# main.net
KiCad netlist of a schematic drawn in Altium Designer
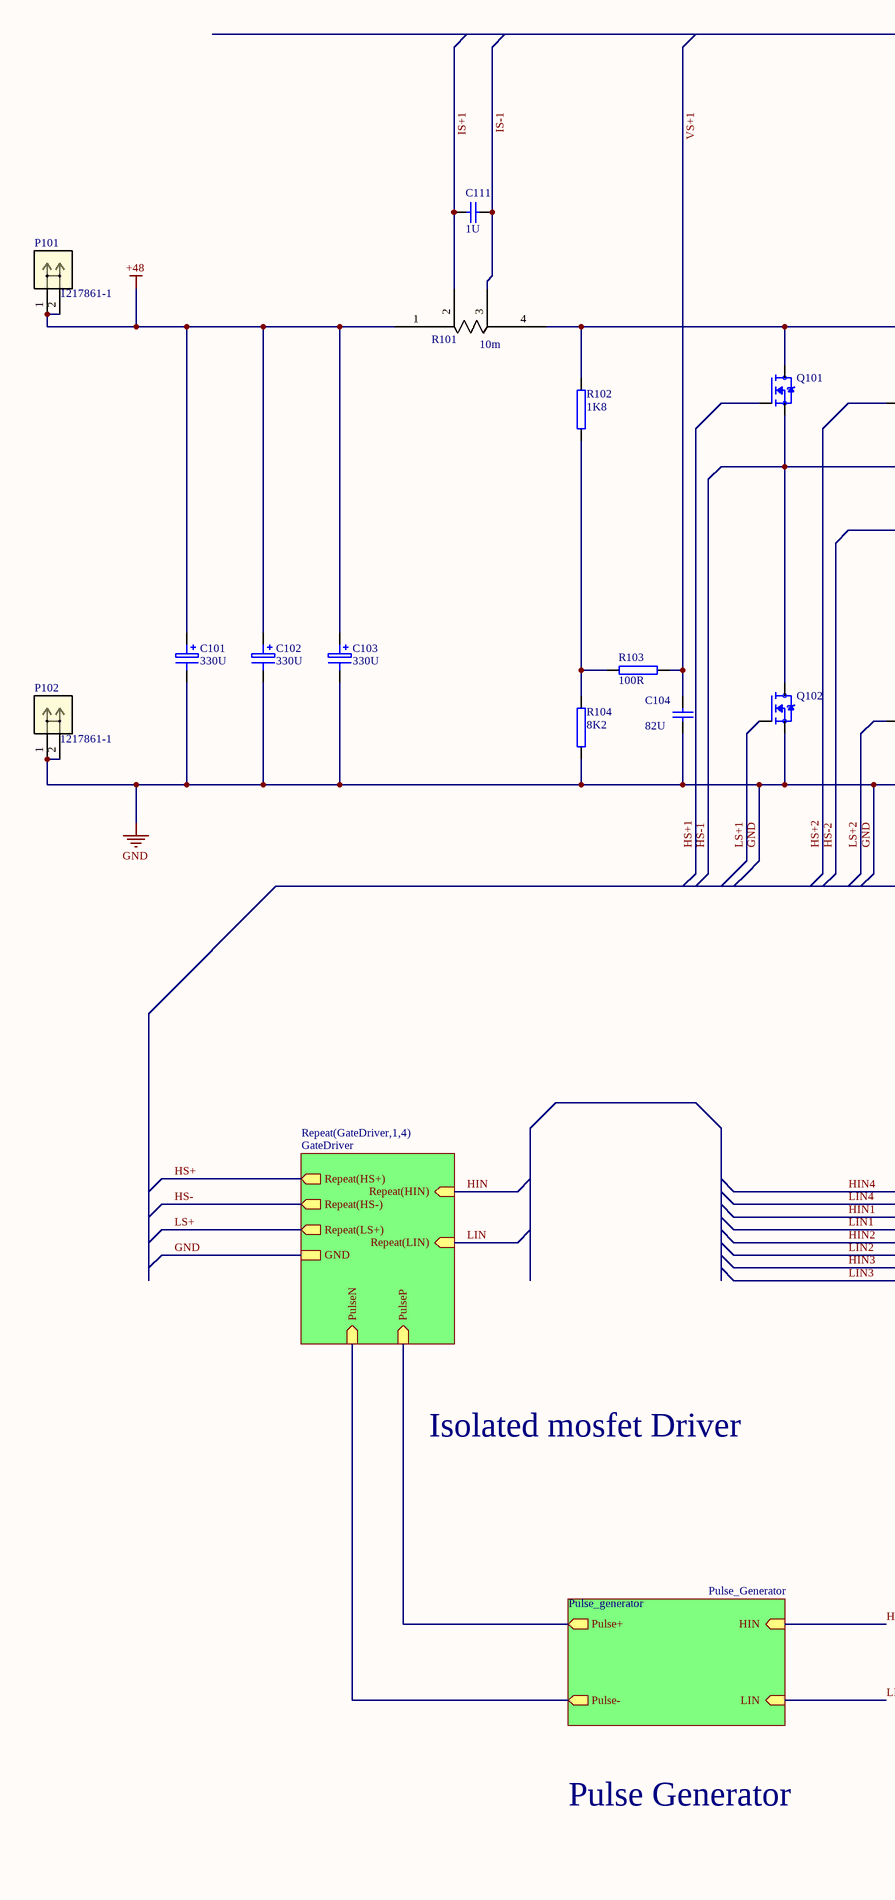
[diagram p0: main.SchDoc, left]
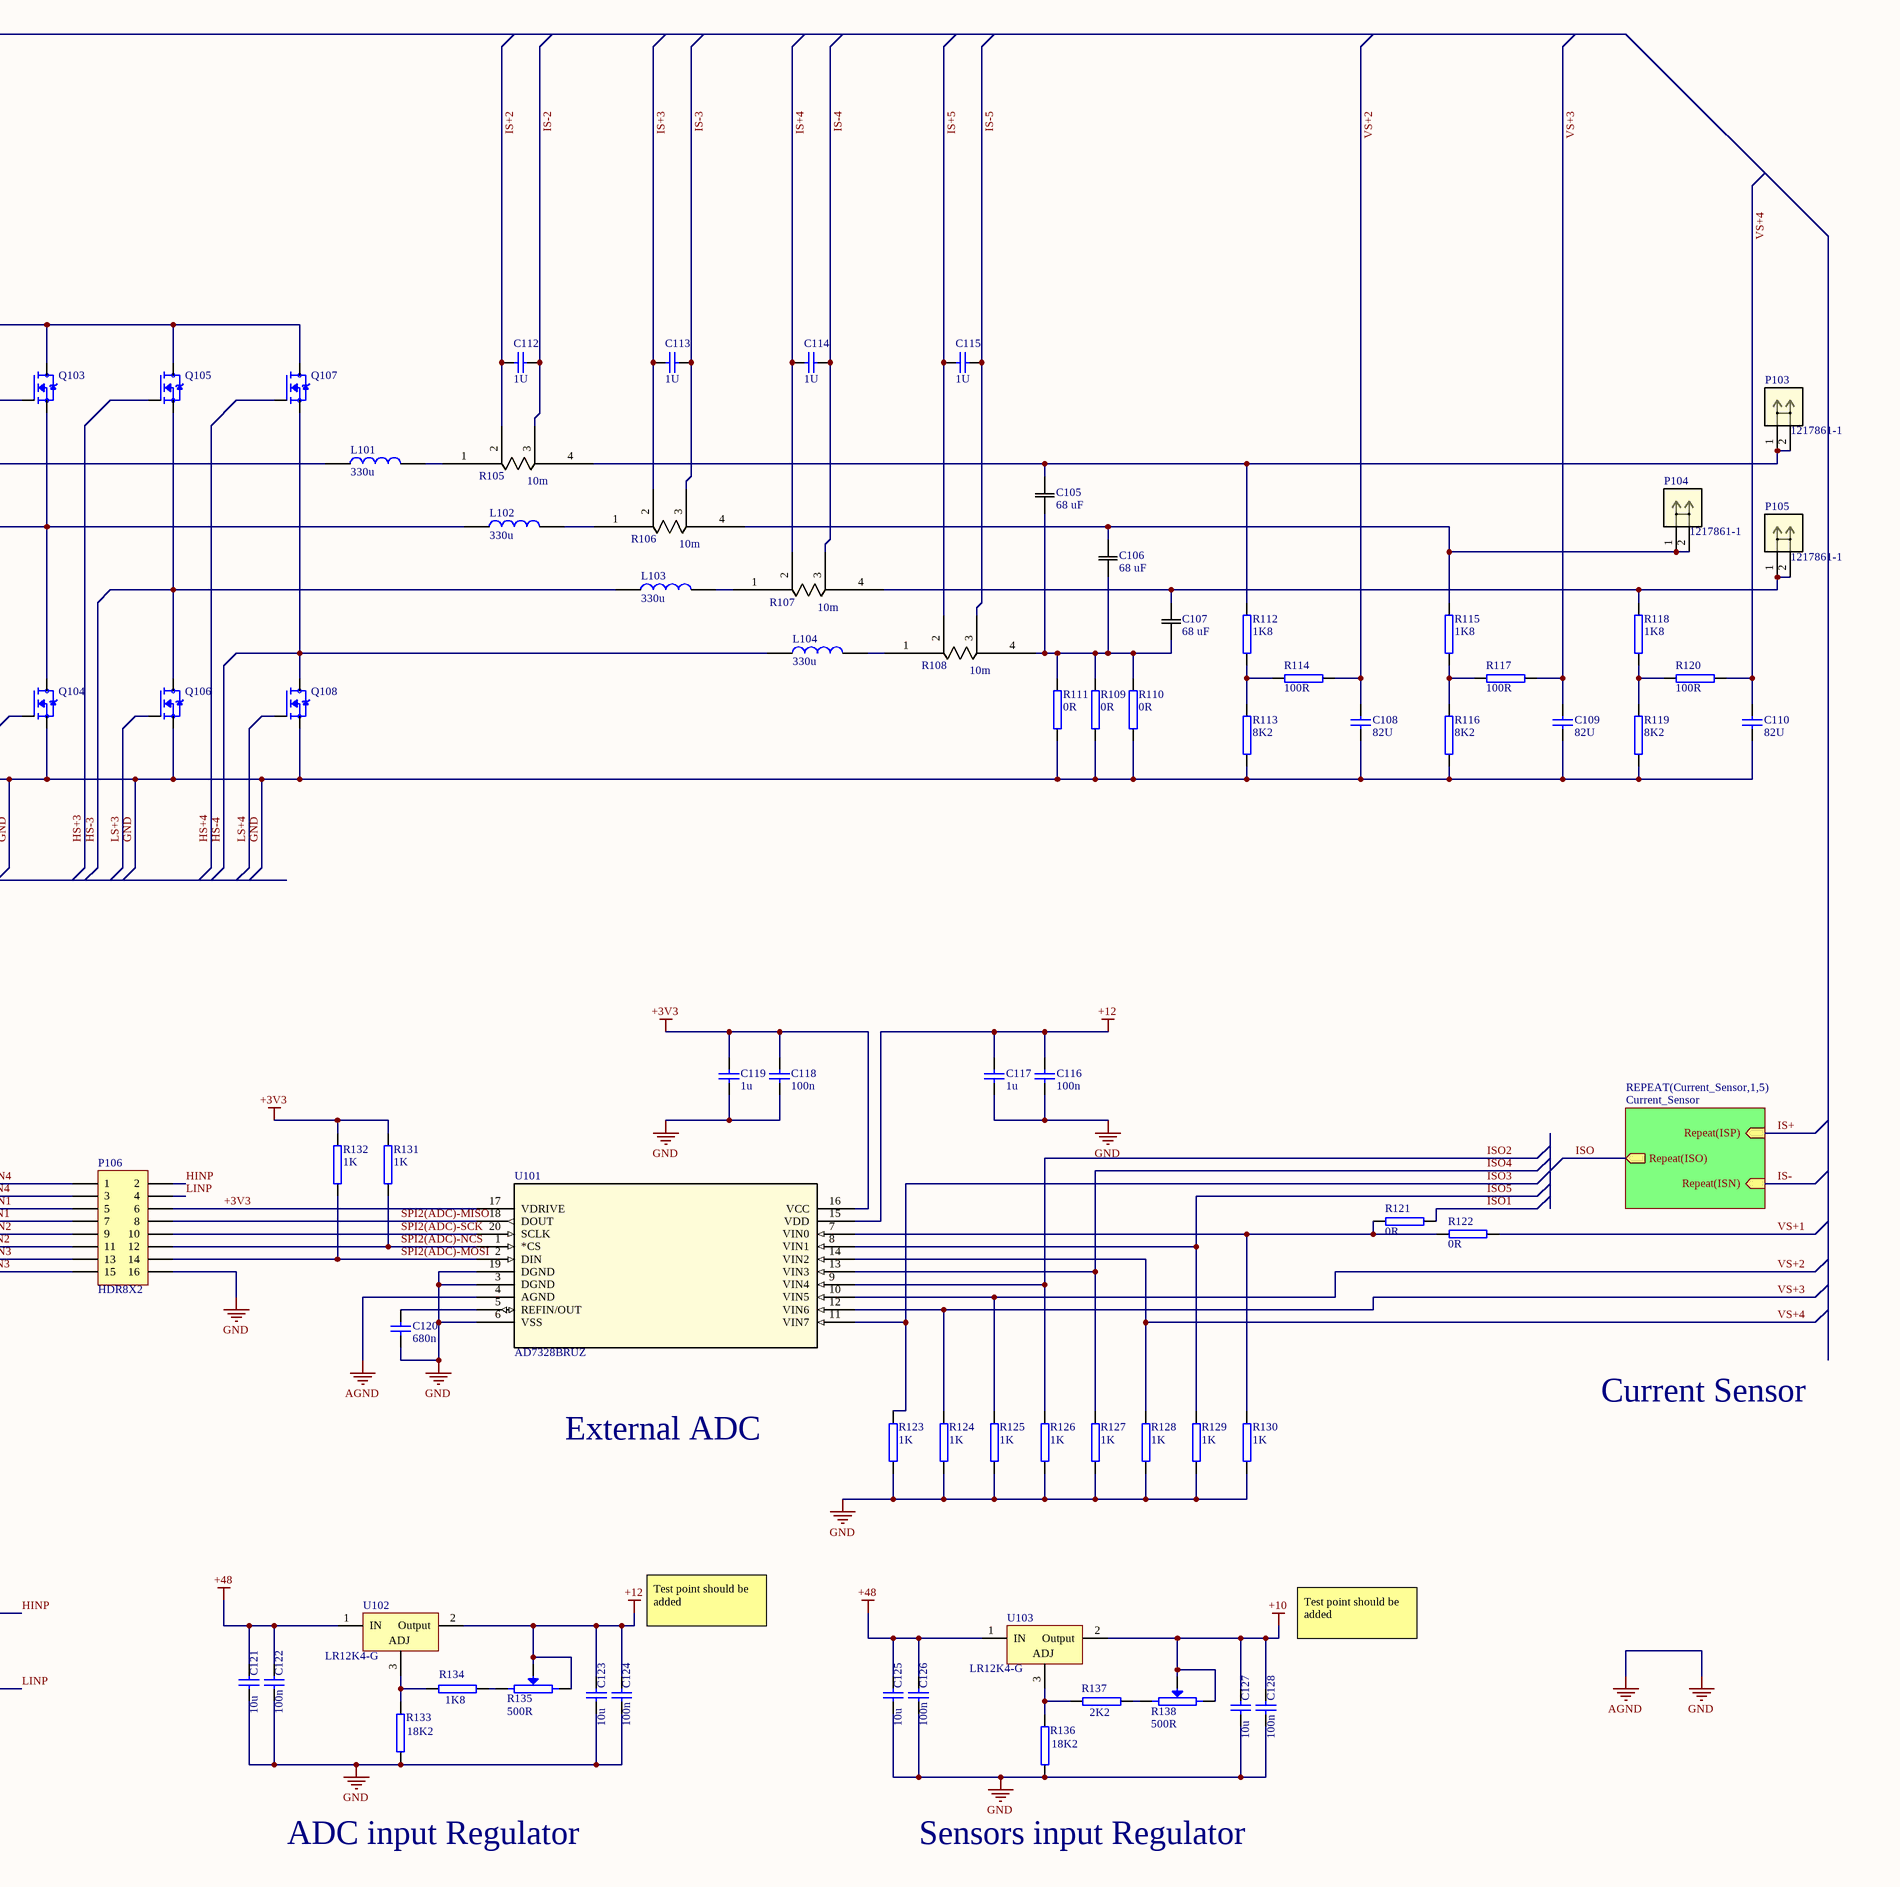
[diagram p1: main.SchDoc, right]

(export (version "E")
  (design (tool "Eeschema 10.0.6"))
  (components
    (comp (ref "C101")
      (value "330U")
      (footprint "CAPP300-600_AUT")
      (description "Polarized Aluminum Capacitor, Through Hole, Pitch 300mil, Body 600mil (Dia)")
      (libsource (lib "Resistors and Capacitors") (part "CAPP300-600"))
    )
    (comp (ref "C102")
      (value "330U")
      (footprint "CAPP300-600_AUT")
      (description "Polarized Aluminum Capacitor, Through Hole, Pitch 300mil, Body 600mil (Dia)")
      (libsource (lib "Resistors and Capacitors") (part "CAPP300-600"))
    )
    (comp (ref "C103")
      (value "330U")
      (footprint "CAPP300-600_AUT")
      (description "Polarized Aluminum Capacitor, Through Hole, Pitch 300mil, Body 600mil (Dia)")
      (libsource (lib "Resistors and Capacitors") (part "CAPP300-600"))
    )
    (comp (ref "C104")
      (value "82U")
      (footprint "CAP_1206")
      (description "Non Polarized Capacitor, SMD, 1206")
      (libsource (lib "Resistors and Capacitors") (part "CAPN 1206"))
    )
    (comp (ref "C105")
      (value "68 uF")
      (footprint "B32526R3686K000")
      (libsource (lib "ENEL709_Schematic_Library") (part "B32526R3686K000"))
    )
    (comp (ref "C106")
      (value "68 uF")
      (footprint "B32526R3686K000")
      (libsource (lib "ENEL709_Schematic_Library") (part "B32526R3686K000"))
    )
    (comp (ref "C107")
      (value "68 uF")
      (footprint "B32526R3686K000")
      (libsource (lib "ENEL709_Schematic_Library") (part "B32526R3686K000"))
    )
    (comp (ref "C108")
      (value "82U")
      (footprint "CAP_1206")
      (description "Non Polarized Capacitor, SMD, 1206")
      (libsource (lib "Resistors and Capacitors") (part "CAPN 1206"))
    )
    (comp (ref "C109")
      (value "82U")
      (footprint "CAP_1206")
      (description "Non Polarized Capacitor, SMD, 1206")
      (libsource (lib "Resistors and Capacitors") (part "CAPN 1206"))
    )
    (comp (ref "C110")
      (value "82U")
      (footprint "CAP_1206")
      (description "Non Polarized Capacitor, SMD, 1206")
      (libsource (lib "Resistors and Capacitors") (part "CAPN 1206"))
    )
    (comp (ref "C111")
      (value "1U")
      (footprint "CAP_1206")
      (description "Non Polarized Capacitor, SMD, 1206")
      (libsource (lib "Resistors and Capacitors") (part "CAPN 1206"))
    )
    (comp (ref "C112")
      (value "1U")
      (footprint "CAP_1206")
      (description "Non Polarized Capacitor, SMD, 1206")
      (libsource (lib "Resistors and Capacitors") (part "CAPN 1206"))
    )
    (comp (ref "C113")
      (value "1U")
      (footprint "CAP_1206")
      (description "Non Polarized Capacitor, SMD, 1206")
      (libsource (lib "Resistors and Capacitors") (part "CAPN 1206"))
    )
    (comp (ref "C114")
      (value "1U")
      (footprint "CAP_1206")
      (description "Non Polarized Capacitor, SMD, 1206")
      (libsource (lib "Resistors and Capacitors") (part "CAPN 1206"))
    )
    (comp (ref "C115")
      (value "1U")
      (footprint "CAP_1206")
      (description "Non Polarized Capacitor, SMD, 1206")
      (libsource (lib "Resistors and Capacitors") (part "CAPN 1206"))
    )
    (comp (ref "C116")
      (value "100n")
      (footprint "CAP_1206")
      (description "Non Polarized Capacitor, SMD, 1206")
      (libsource (lib "Resistors and Capacitors") (part "CAPN 1206"))
    )
    (comp (ref "C117")
      (value "1u")
      (footprint "CAP_1206")
      (description "Non Polarized Capacitor, SMD, 1206")
      (libsource (lib "Resistors and Capacitors") (part "CAPN 1206"))
    )
    (comp (ref "C118")
      (value "100n")
      (footprint "CAP_1206")
      (description "Non Polarized Capacitor, SMD, 1206")
      (libsource (lib "Resistors and Capacitors") (part "CAPN 1206"))
    )
    (comp (ref "C119")
      (value "1u")
      (footprint "CAP_1206")
      (description "Non Polarized Capacitor, SMD, 1206")
      (libsource (lib "Resistors and Capacitors") (part "CAPN 1206"))
    )
    (comp (ref "C120")
      (value "680n")
      (footprint "CAP_1206")
      (description "Non Polarized Capacitor, SMD, 1206")
      (libsource (lib "Resistors and Capacitors") (part "CAPN 1206"))
    )
    (comp (ref "C121")
      (value "10u")
      (footprint "CAP_1206")
      (description "Non Polarized Capacitor, SMD, 1206")
      (libsource (lib "Resistors and Capacitors") (part "CAPN 1206"))
    )
    (comp (ref "C122")
      (value "100n")
      (footprint "CAP_1206")
      (description "Non Polarized Capacitor, SMD, 1206")
      (libsource (lib "Resistors and Capacitors") (part "CAPN 1206"))
    )
    (comp (ref "C123")
      (value "10u")
      (footprint "CAP_1206")
      (description "Non Polarized Capacitor, SMD, 1206")
      (libsource (lib "Resistors and Capacitors") (part "CAPN 1206"))
    )
    (comp (ref "C124")
      (value "100n")
      (footprint "CAP_1206")
      (description "Non Polarized Capacitor, SMD, 1206")
      (libsource (lib "Resistors and Capacitors") (part "CAPN 1206"))
    )
    (comp (ref "C125")
      (value "10u")
      (footprint "CAP_1206")
      (description "Non Polarized Capacitor, SMD, 1206")
      (libsource (lib "Resistors and Capacitors") (part "CAPN 1206"))
    )
    (comp (ref "C126")
      (value "100n")
      (footprint "CAP_1206")
      (description "Non Polarized Capacitor, SMD, 1206")
      (libsource (lib "Resistors and Capacitors") (part "CAPN 1206"))
    )
    (comp (ref "C127")
      (value "10u")
      (footprint "CAP_1206")
      (description "Non Polarized Capacitor, SMD, 1206")
      (libsource (lib "Resistors and Capacitors") (part "CAPN 1206"))
    )
    (comp (ref "C128")
      (value "100n")
      (footprint "CAP_1206")
      (description "Non Polarized Capacitor, SMD, 1206")
      (libsource (lib "Resistors and Capacitors") (part "CAPN 1206"))
    )
    (comp (ref "L101")
      (value "330u")
      (footprint "1140-331K-RC")
      (libsource (lib "ENEL709_Schematic_Library") (part "1140-331K-RC"))
    )
    (comp (ref "L102")
      (value "330u")
      (footprint "1140-331K-RC")
      (libsource (lib "ENEL709_Schematic_Library") (part "1140-331K-RC"))
    )
    (comp (ref "L103")
      (value "330u")
      (footprint "1140-331K-RC")
      (libsource (lib "ENEL709_Schematic_Library") (part "1140-331K-RC"))
    )
    (comp (ref "L104")
      (value "330u")
      (footprint "1140-331K-RC")
      (libsource (lib "ENEL709_Schematic_Library") (part "1140-331K-RC"))
    )
    (comp (ref "P101")
      (value "1217861-1")
      (footprint "CONN_1217861-1_TEC")
      (libsource (lib "ENEL709_Schematic_Library") (part "1217861-1"))
    )
    (comp (ref "P102")
      (value "1217861-1")
      (footprint "CONN_1217861-1_TEC")
      (libsource (lib "ENEL709_Schematic_Library") (part "1217861-1"))
    )
    (comp (ref "P103")
      (value "1217861-1")
      (footprint "CONN_1217861-1_TEC")
      (libsource (lib "ENEL709_Schematic_Library") (part "1217861-1"))
    )
    (comp (ref "P104")
      (value "1217861-1")
      (footprint "CONN_1217861-1_TEC")
      (libsource (lib "ENEL709_Schematic_Library") (part "1217861-1"))
    )
    (comp (ref "P105")
      (value "1217861-1")
      (footprint "CONN_1217861-1_TEC")
      (libsource (lib "ENEL709_Schematic_Library") (part "1217861-1"))
    )
    (comp (ref "P106")
      (value "HDR8X2")
      (footprint "HDR2X8_AUT")
      (description "Header, 8-Pin, Dual row, 2.54mm Pitch, Straight")
      (libsource (lib "Connectors") (part "HDR8X2"))
    )
    (comp (ref "Q101")
      (value "MCTL80N20Y-TP")
      (footprint "TOLL-8L")
      (description "N-Channel 200 V 80A (Tc) 250W (Tj) Surface Mount TOLL-8L")
      (libsource (lib "Projects_2025") (part "MCTL80N20Y-TP"))
    )
    (comp (ref "Q102")
      (value "MCTL80N20Y-TP")
      (footprint "TOLL-8L")
      (description "N-Channel 200 V 80A (Tc) 250W (Tj) Surface Mount TOLL-8L")
      (libsource (lib "Projects_2025") (part "MCTL80N20Y-TP"))
    )
    (comp (ref "Q103")
      (value "MCTL80N20Y-TP")
      (footprint "TOLL-8L")
      (description "N-Channel 200 V 80A (Tc) 250W (Tj) Surface Mount TOLL-8L")
      (libsource (lib "Projects_2025") (part "MCTL80N20Y-TP"))
    )
    (comp (ref "Q104")
      (value "MCTL80N20Y-TP")
      (footprint "TOLL-8L")
      (description "N-Channel 200 V 80A (Tc) 250W (Tj) Surface Mount TOLL-8L")
      (libsource (lib "Projects_2025") (part "MCTL80N20Y-TP"))
    )
    (comp (ref "Q105")
      (value "MCTL80N20Y-TP")
      (footprint "TOLL-8L")
      (description "N-Channel 200 V 80A (Tc) 250W (Tj) Surface Mount TOLL-8L")
      (libsource (lib "Projects_2025") (part "MCTL80N20Y-TP"))
    )
    (comp (ref "Q106")
      (value "MCTL80N20Y-TP")
      (footprint "TOLL-8L")
      (description "N-Channel 200 V 80A (Tc) 250W (Tj) Surface Mount TOLL-8L")
      (libsource (lib "Projects_2025") (part "MCTL80N20Y-TP"))
    )
    (comp (ref "Q107")
      (value "MCTL80N20Y-TP")
      (footprint "TOLL-8L")
      (description "N-Channel 200 V 80A (Tc) 250W (Tj) Surface Mount TOLL-8L")
      (libsource (lib "Projects_2025") (part "MCTL80N20Y-TP"))
    )
    (comp (ref "Q108")
      (value "MCTL80N20Y-TP")
      (footprint "TOLL-8L")
      (description "N-Channel 200 V 80A (Tc) 250W (Tj) Surface Mount TOLL-8L")
      (libsource (lib "Projects_2025") (part "MCTL80N20Y-TP"))
    )
    (comp (ref "R101")
      (value "10m")
      (footprint "WSL3673R_002-01")
      (description "Current Shunt \r\nKelvin 4W 0.002- 0.01")
      (libsource (lib "Projects_2025") (part "WSL3673R-01"))
    )
    (comp (ref "R102")
      (value "1K8")
      (footprint "RES_1206")
      (description "Resistor, SMD, 1206")
      (libsource (lib "Resistors and Capacitors") (part "Resistor 1206"))
    )
    (comp (ref "R103")
      (value "100R")
      (footprint "RES_1206")
      (description "Resistor, SMD, 1206")
      (libsource (lib "Resistors and Capacitors") (part "Resistor 1206"))
    )
    (comp (ref "R104")
      (value "8K2")
      (footprint "RES_1206")
      (description "Resistor, SMD, 1206")
      (libsource (lib "Resistors and Capacitors") (part "Resistor 1206"))
    )
    (comp (ref "R105")
      (value "10m")
      (footprint "WSL3673R_002-01")
      (description "Current Shunt \r\nKelvin 4W 0.002- 0.01")
      (libsource (lib "Projects_2025") (part "WSL3673R-01"))
    )
    (comp (ref "R106")
      (value "10m")
      (footprint "WSL3673R_002-01")
      (description "Current Shunt \r\nKelvin 4W 0.002- 0.01")
      (libsource (lib "Projects_2025") (part "WSL3673R-01"))
    )
    (comp (ref "R107")
      (value "10m")
      (footprint "WSL3673R_002-01")
      (description "Current Shunt \r\nKelvin 4W 0.002- 0.01")
      (libsource (lib "Projects_2025") (part "WSL3673R-01"))
    )
    (comp (ref "R108")
      (value "10m")
      (footprint "WSL3673R_002-01")
      (description "Current Shunt \r\nKelvin 4W 0.002- 0.01")
      (libsource (lib "Projects_2025") (part "WSL3673R-01"))
    )
    (comp (ref "R109")
      (value "0R")
      (footprint "RES_1206")
      (description "Resistor, SMD, 1206")
      (libsource (lib "Resistors and Capacitors") (part "Resistor 1206"))
    )
    (comp (ref "R110")
      (value "0R")
      (footprint "RES_1206")
      (description "Resistor, SMD, 1206")
      (libsource (lib "Resistors and Capacitors") (part "Resistor 1206"))
    )
    (comp (ref "R111")
      (value "0R")
      (footprint "RES_1206")
      (description "Resistor, SMD, 1206")
      (libsource (lib "Resistors and Capacitors") (part "Resistor 1206"))
    )
    (comp (ref "R112")
      (value "1K8")
      (footprint "RES_1206")
      (description "Resistor, SMD, 1206")
      (libsource (lib "Resistors and Capacitors") (part "Resistor 1206"))
    )
    (comp (ref "R113")
      (value "8K2")
      (footprint "RES_1206")
      (description "Resistor, SMD, 1206")
      (libsource (lib "Resistors and Capacitors") (part "Resistor 1206"))
    )
    (comp (ref "R114")
      (value "100R")
      (footprint "RES_1206")
      (description "Resistor, SMD, 1206")
      (libsource (lib "Resistors and Capacitors") (part "Resistor 1206"))
    )
    (comp (ref "R115")
      (value "1K8")
      (footprint "RES_1206")
      (description "Resistor, SMD, 1206")
      (libsource (lib "Resistors and Capacitors") (part "Resistor 1206"))
    )
    (comp (ref "R116")
      (value "8K2")
      (footprint "RES_1206")
      (description "Resistor, SMD, 1206")
      (libsource (lib "Resistors and Capacitors") (part "Resistor 1206"))
    )
    (comp (ref "R117")
      (value "100R")
      (footprint "RES_1206")
      (description "Resistor, SMD, 1206")
      (libsource (lib "Resistors and Capacitors") (part "Resistor 1206"))
    )
    (comp (ref "R118")
      (value "1K8")
      (footprint "RES_1206")
      (description "Resistor, SMD, 1206")
      (libsource (lib "Resistors and Capacitors") (part "Resistor 1206"))
    )
    (comp (ref "R119")
      (value "8K2")
      (footprint "RES_1206")
      (description "Resistor, SMD, 1206")
      (libsource (lib "Resistors and Capacitors") (part "Resistor 1206"))
    )
    (comp (ref "R120")
      (value "100R")
      (footprint "RES_1206")
      (description "Resistor, SMD, 1206")
      (libsource (lib "Resistors and Capacitors") (part "Resistor 1206"))
    )
    (comp (ref "R121")
      (value "0R")
      (footprint "RES_1206")
      (description "Resistor, SMD, 1206")
      (libsource (lib "Resistors and Capacitors") (part "Resistor 1206"))
    )
    (comp (ref "R122")
      (value "0R")
      (footprint "RES_1206")
      (description "Resistor, SMD, 1206")
      (libsource (lib "Resistors and Capacitors") (part "Resistor 1206"))
    )
    (comp (ref "R123")
      (value "1K")
      (footprint "RES_1206")
      (description "Resistor, SMD, 1206")
      (libsource (lib "Resistors and Capacitors") (part "Resistor 1206"))
    )
    (comp (ref "R124")
      (value "1K")
      (footprint "RES_1206")
      (description "Resistor, SMD, 1206")
      (libsource (lib "Resistors and Capacitors") (part "Resistor 1206"))
    )
    (comp (ref "R125")
      (value "1K")
      (footprint "RES_1206")
      (description "Resistor, SMD, 1206")
      (libsource (lib "Resistors and Capacitors") (part "Resistor 1206"))
    )
    (comp (ref "R126")
      (value "1K")
      (footprint "RES_1206")
      (description "Resistor, SMD, 1206")
      (libsource (lib "Resistors and Capacitors") (part "Resistor 1206"))
    )
    (comp (ref "R127")
      (value "1K")
      (footprint "RES_1206")
      (description "Resistor, SMD, 1206")
      (libsource (lib "Resistors and Capacitors") (part "Resistor 1206"))
    )
    (comp (ref "R128")
      (value "1K")
      (footprint "RES_1206")
      (description "Resistor, SMD, 1206")
      (libsource (lib "Resistors and Capacitors") (part "Resistor 1206"))
    )
    (comp (ref "R129")
      (value "1K")
      (footprint "RES_1206")
      (description "Resistor, SMD, 1206")
      (libsource (lib "Resistors and Capacitors") (part "Resistor 1206"))
    )
    (comp (ref "R130")
      (value "1K")
      (footprint "RES_1206")
      (description "Resistor, SMD, 1206")
      (libsource (lib "Resistors and Capacitors") (part "Resistor 1206"))
    )
    (comp (ref "R131")
      (value "1K")
      (footprint "RES_1206")
      (description "Resistor, SMD, 1206")
      (libsource (lib "Resistors and Capacitors") (part "Resistor 1206"))
    )
    (comp (ref "R132")
      (value "1K")
      (footprint "RES_1206")
      (description "Resistor, SMD, 1206")
      (libsource (lib "Resistors and Capacitors") (part "Resistor 1206"))
    )
    (comp (ref "R133")
      (value "18K2")
      (footprint "RES_1206")
      (description "Resistor, SMD, 1206")
      (libsource (lib "Resistors and Capacitors") (part "Resistor 1206"))
    )
    (comp (ref "R134")
      (value "1K8")
      (footprint "RES_1206")
      (description "Resistor, SMD, 1206")
      (libsource (lib "Resistors and Capacitors") (part "Resistor 1206"))
    )
    (comp (ref "R135")
      (value "500R")
      (footprint "3296W")
      (libsource (lib "Potentiometers") (part "3296W-1-104LF"))
    )
    (comp (ref "R136")
      (value "18K2")
      (footprint "RES_1206")
      (description "Resistor, SMD, 1206")
      (libsource (lib "Resistors and Capacitors") (part "Resistor 1206"))
    )
    (comp (ref "R137")
      (value "2K2")
      (footprint "RES_1206")
      (description "Resistor, SMD, 1206")
      (libsource (lib "Resistors and Capacitors") (part "Resistor 1206"))
    )
    (comp (ref "R138")
      (value "500R")
      (footprint "3296W")
      (libsource (lib "Potentiometers") (part "3296W-1-104LF"))
    )
    (comp (ref "U101")
      (value "AD7328BRUZ")
      (footprint "TSSOP20_44")
      (description "ADC 12 Bit\r\nPackage TSSOP20")
      (libsource (lib "Projects_2025") (part "AD7328BRUZ"))
    )
    (comp (ref "U102")
      (value "LR12K4-G")
      (footprint "D PAK (TO-252-3)")
      (description "Adj Positive Regulator \r\nLinear. 12V dropout V. \r\n2W")
      (libsource (lib "Projects_2025") (part "LR12K4-G"))
    )
    (comp (ref "U103")
      (value "LR12K4-G")
      (footprint "D PAK (TO-252-3)")
      (description "Adj Positive Regulator \r\nLinear. 12V dropout V. \r\n2W")
      (libsource (lib "Projects_2025") (part "LR12K4-G"))
    )
  )
  (nets
    (net (code "1") (name "+3V3") (class "Default")
      (node (ref "C118") (pin "2") (pinfunction "2_2") (pintype "passive"))
      (node (ref "C119") (pin "2") (pinfunction "2_2") (pintype "passive"))
      (node (ref "P106") (pin "6") (pinfunction "6_6") (pintype "passive"))
      (node (ref "R131") (pin "2") (pinfunction "2_2") (pintype "passive"))
      (node (ref "R132") (pin "2") (pinfunction "2_2") (pintype "passive"))
      (node (ref "U101") (pin "16") (pinfunction "VCC_16") (pintype "power_in"))
      (node (ref "U101") (pin "17") (pinfunction "VDRIVE_17") (pintype "power_in"))
    )
    (net (code "2") (name "+10") (class "Default")
      (node (ref "C127") (pin "2") (pinfunction "2_2") (pintype "passive"))
      (node (ref "C128") (pin "2") (pinfunction "2_2") (pintype "passive"))
      (node (ref "R138") (pin "2") (pinfunction "BOT_2") (pintype "passive"))
      (node (ref "R138") (pin "W") (pinfunction "TAP_W") (pintype "passive"))
      (node (ref "U103") (pin "2") (pinfunction "Output_2") (pintype "power_in"))
    )
    (net (code "3") (name "+12") (class "Default")
      (node (ref "C116") (pin "2") (pinfunction "2_2") (pintype "passive"))
      (node (ref "C117") (pin "2") (pinfunction "2_2") (pintype "passive"))
      (node (ref "C123") (pin "2") (pinfunction "2_2") (pintype "passive"))
      (node (ref "C124") (pin "2") (pinfunction "2_2") (pintype "passive"))
      (node (ref "R135") (pin "2") (pinfunction "BOT_2") (pintype "passive"))
      (node (ref "R135") (pin "W") (pinfunction "TAP_W") (pintype "passive"))
      (node (ref "U101") (pin "15") (pinfunction "VDD_15") (pintype "power_in"))
      (node (ref "U102") (pin "2") (pinfunction "Output_2") (pintype "power_in"))
    )
    (net (code "4") (name "+48") (class "Default")
      (node (ref "C101") (pin "1") (pinfunction "1_1") (pintype "passive"))
      (node (ref "C102") (pin "1") (pinfunction "1_1") (pintype "passive"))
      (node (ref "C103") (pin "1") (pinfunction "1_1") (pintype "passive"))
      (node (ref "C121") (pin "2") (pinfunction "2_2") (pintype "passive"))
      (node (ref "C122") (pin "2") (pinfunction "2_2") (pintype "passive"))
      (node (ref "C125") (pin "2") (pinfunction "2_2") (pintype "passive"))
      (node (ref "C126") (pin "2") (pinfunction "2_2") (pintype "passive"))
      (node (ref "P101") (pin "1") (pinfunction "1_1") (pintype "passive"))
      (node (ref "P101") (pin "2") (pinfunction "2_2") (pintype "passive"))
      (node (ref "R101") (pin "1") (pinfunction "1_1") (pintype "passive"))
      (node (ref "U102") (pin "1") (pinfunction "IN_1") (pintype "power_in"))
      (node (ref "U103") (pin "1") (pinfunction "IN_1") (pintype "power_in"))
    )
    (net (code "6") (name "/HIN1") (class "Default")
      (node (ref "P106") (pin "5") (pinfunction "5_5") (pintype "passive"))
    )
    (net (code "7") (name "/HIN2") (class "Default")
      (node (ref "P106") (pin "9") (pinfunction "9_9") (pintype "passive"))
    )
    (net (code "8") (name "/HIN3") (class "Default")
      (node (ref "P106") (pin "13") (pinfunction "13_13") (pintype "passive"))
    )
    (net (code "9") (name "/HIN4") (class "Default")
      (node (ref "P106") (pin "1") (pinfunction "1_1") (pintype "passive"))
    )
    (net (code "10") (name "/HINP") (class "Default")
      (node (ref "P106") (pin "2") (pinfunction "2_2") (pintype "passive"))
    )
    (net (code "12") (name "/HS+1") (class "Default")
      (node (ref "Q101") (pin "1") (pinfunction "G_1") (pintype "passive"))
    )
    (net (code "13") (name "/HS+2") (class "Default")
      (node (ref "Q103") (pin "1") (pinfunction "G_1") (pintype "passive"))
    )
    (net (code "14") (name "/HS+3") (class "Default")
      (node (ref "Q105") (pin "1") (pinfunction "G_1") (pintype "passive"))
    )
    (net (code "15") (name "/HS+4") (class "Default")
      (node (ref "Q107") (pin "1") (pinfunction "G_1") (pintype "passive"))
    )
    (net (code "17") (name "/HS-1") (class "Default")
      (node (ref "L101") (pin "1") (pinfunction "1_1") (pintype "passive"))
      (node (ref "Q101") (pin "2") (pinfunction "S_2") (pintype "passive"))
      (node (ref "Q102") (pin "3") (pinfunction "D_3") (pintype "passive"))
    )
    (net (code "18") (name "/HS-2") (class "Default")
      (node (ref "L102") (pin "1") (pinfunction "1_1") (pintype "passive"))
      (node (ref "Q103") (pin "2") (pinfunction "S_2") (pintype "passive"))
      (node (ref "Q104") (pin "3") (pinfunction "D_3") (pintype "passive"))
    )
    (net (code "19") (name "/HS-3") (class "Default")
      (node (ref "L103") (pin "1") (pinfunction "1_1") (pintype "passive"))
      (node (ref "Q105") (pin "2") (pinfunction "S_2") (pintype "passive"))
      (node (ref "Q106") (pin "3") (pinfunction "D_3") (pintype "passive"))
    )
    (net (code "20") (name "/HS-4") (class "Default")
      (node (ref "L104") (pin "1") (pinfunction "1_1") (pintype "passive"))
      (node (ref "Q107") (pin "2") (pinfunction "S_2") (pintype "passive"))
      (node (ref "Q108") (pin "3") (pinfunction "D_3") (pintype "passive"))
    )
    (net (code "22") (name "/IS+1") (class "Default")
      (node (ref "C111") (pin "2") (pinfunction "2_2") (pintype "passive"))
      (node (ref "R101") (pin "2") (pinfunction "2_2") (pintype "passive"))
    )
    (net (code "23") (name "/IS+2") (class "Default")
      (node (ref "C112") (pin "2") (pinfunction "2_2") (pintype "passive"))
      (node (ref "R105") (pin "2") (pinfunction "2_2") (pintype "passive"))
    )
    (net (code "24") (name "/IS+3") (class "Default")
      (node (ref "C113") (pin "2") (pinfunction "2_2") (pintype "passive"))
      (node (ref "R106") (pin "2") (pinfunction "2_2") (pintype "passive"))
    )
    (net (code "25") (name "/IS+4") (class "Default")
      (node (ref "C114") (pin "2") (pinfunction "2_2") (pintype "passive"))
      (node (ref "R107") (pin "2") (pinfunction "2_2") (pintype "passive"))
    )
    (net (code "26") (name "/IS+5") (class "Default")
      (node (ref "C115") (pin "2") (pinfunction "2_2") (pintype "passive"))
      (node (ref "R108") (pin "2") (pinfunction "2_2") (pintype "passive"))
    )
    (net (code "28") (name "/IS-1") (class "Default")
      (node (ref "C111") (pin "1") (pinfunction "1_1") (pintype "passive"))
      (node (ref "R101") (pin "3") (pinfunction "3_3") (pintype "passive"))
    )
    (net (code "29") (name "/IS-2") (class "Default")
      (node (ref "C112") (pin "1") (pinfunction "1_1") (pintype "passive"))
      (node (ref "R105") (pin "3") (pinfunction "3_3") (pintype "passive"))
    )
    (net (code "30") (name "/IS-3") (class "Default")
      (node (ref "C113") (pin "1") (pinfunction "1_1") (pintype "passive"))
      (node (ref "R106") (pin "3") (pinfunction "3_3") (pintype "passive"))
    )
    (net (code "31") (name "/IS-4") (class "Default")
      (node (ref "C114") (pin "1") (pinfunction "1_1") (pintype "passive"))
      (node (ref "R107") (pin "3") (pinfunction "3_3") (pintype "passive"))
    )
    (net (code "32") (name "/IS-5") (class "Default")
      (node (ref "C115") (pin "1") (pinfunction "1_1") (pintype "passive"))
      (node (ref "R108") (pin "3") (pinfunction "3_3") (pintype "passive"))
    )
    (net (code "34") (name "/ISO1") (class "Default")
      (node (ref "R121") (pin "2") (pinfunction "2_2") (pintype "passive"))
    )
    (net (code "35") (name "/ISO2") (class "Default")
      (node (ref "R126") (pin "2") (pinfunction "2_2") (pintype "passive"))
      (node (ref "U101") (pin "9") (pinfunction "VIN4_9") (pintype "input"))
    )
    (net (code "36") (name "/ISO3") (class "Default")
      (node (ref "R123") (pin "2") (pinfunction "2_2") (pintype "passive"))
      (node (ref "U101") (pin "11") (pinfunction "VIN7_11") (pintype "input"))
    )
    (net (code "37") (name "/ISO4") (class "Default")
      (node (ref "R127") (pin "2") (pinfunction "2_2") (pintype "passive"))
      (node (ref "U101") (pin "13") (pinfunction "VIN3_13") (pintype "input"))
    )
    (net (code "38") (name "/ISO5") (class "Default")
      (node (ref "R129") (pin "2") (pinfunction "2_2") (pintype "passive"))
      (node (ref "U101") (pin "8") (pinfunction "VIN1_8") (pintype "input"))
    )
    (net (code "40") (name "/LIN1") (class "Default")
      (node (ref "P106") (pin "7") (pinfunction "7_7") (pintype "passive"))
    )
    (net (code "41") (name "/LIN2") (class "Default")
      (node (ref "P106") (pin "11") (pinfunction "11_11") (pintype "passive"))
    )
    (net (code "42") (name "/LIN3") (class "Default")
      (node (ref "P106") (pin "15") (pinfunction "15_15") (pintype "passive"))
    )
    (net (code "43") (name "/LIN4") (class "Default")
      (node (ref "P106") (pin "3") (pinfunction "3_3") (pintype "passive"))
    )
    (net (code "44") (name "/LINP") (class "Default")
      (node (ref "P106") (pin "4") (pinfunction "4_4") (pintype "passive"))
    )
    (net (code "46") (name "/LS+1") (class "Default")
      (node (ref "Q102") (pin "1") (pinfunction "G_1") (pintype "passive"))
    )
    (net (code "47") (name "/LS+2") (class "Default")
      (node (ref "Q104") (pin "1") (pinfunction "G_1") (pintype "passive"))
    )
    (net (code "48") (name "/LS+3") (class "Default")
      (node (ref "Q106") (pin "1") (pinfunction "G_1") (pintype "passive"))
    )
    (net (code "49") (name "/LS+4") (class "Default")
      (node (ref "Q108") (pin "1") (pinfunction "G_1") (pintype "passive"))
    )
    (net (code "52") (name "/SPI2(ADC)-MISO") (class "Default")
      (node (ref "P106") (pin "8") (pinfunction "8_8") (pintype "passive"))
      (node (ref "U101") (pin "18") (pinfunction "DOUT_18") (pintype "output"))
    )
    (net (code "53") (name "/SPI2(ADC)-MOSI") (class "Default")
      (node (ref "P106") (pin "14") (pinfunction "14_14") (pintype "passive"))
      (node (ref "R132") (pin "1") (pinfunction "1_1") (pintype "passive"))
      (node (ref "U101") (pin "2") (pinfunction "DIN_2") (pintype "input"))
    )
    (net (code "54") (name "/SPI2(ADC)-NCS") (class "Default")
      (node (ref "P106") (pin "12") (pinfunction "12_12") (pintype "passive"))
      (node (ref "R131") (pin "1") (pinfunction "1_1") (pintype "passive"))
      (node (ref "U101") (pin "1") (pinfunction "*CS_1") (pintype "input"))
    )
    (net (code "55") (name "/SPI2(ADC)-SCK") (class "Default")
      (node (ref "P106") (pin "10") (pinfunction "10_10") (pintype "passive"))
      (node (ref "U101") (pin "20") (pinfunction "SCLK_20") (pintype "input"))
    )
    (net (code "56") (name "/VS+1") (class "Default")
      (node (ref "C104") (pin "2") (pinfunction "2_2") (pintype "passive"))
      (node (ref "R103") (pin "1") (pinfunction "1_1") (pintype "passive"))
      (node (ref "R122") (pin "2") (pinfunction "2_2") (pintype "passive"))
    )
    (net (code "57") (name "/VS+2") (class "Default")
      (node (ref "C108") (pin "2") (pinfunction "2_2") (pintype "passive"))
      (node (ref "R114") (pin "1") (pinfunction "1_1") (pintype "passive"))
      (node (ref "R125") (pin "2") (pinfunction "2_2") (pintype "passive"))
      (node (ref "U101") (pin "10") (pinfunction "VIN5_10") (pintype "input"))
    )
    (net (code "58") (name "/VS+3") (class "Default")
      (node (ref "C109") (pin "2") (pinfunction "2_2") (pintype "passive"))
      (node (ref "R117") (pin "1") (pinfunction "1_1") (pintype "passive"))
      (node (ref "R124") (pin "2") (pinfunction "2_2") (pintype "passive"))
      (node (ref "U101") (pin "12") (pinfunction "VIN6_12") (pintype "input"))
    )
    (net (code "59") (name "/VS+4") (class "Default")
      (node (ref "C110") (pin "2") (pinfunction "2_2") (pintype "passive"))
      (node (ref "R120") (pin "1") (pinfunction "1_1") (pintype "passive"))
      (node (ref "R128") (pin "2") (pinfunction "2_2") (pintype "passive"))
      (node (ref "U101") (pin "14") (pinfunction "VIN2_14") (pintype "input"))
    )
    (net (code "60") (name "AGND") (class "Default")
      (node (ref "C101") (pin "2") (pinfunction "2_2") (pintype "passive"))
      (node (ref "C102") (pin "2") (pinfunction "2_2") (pintype "passive"))
      (node (ref "C103") (pin "2") (pinfunction "2_2") (pintype "passive"))
      (node (ref "C104") (pin "1") (pinfunction "1_1") (pintype "passive"))
      (node (ref "C108") (pin "1") (pinfunction "1_1") (pintype "passive"))
      (node (ref "C109") (pin "1") (pinfunction "1_1") (pintype "passive"))
      (node (ref "C110") (pin "1") (pinfunction "1_1") (pintype "passive"))
      (node (ref "C116") (pin "1") (pinfunction "1_1") (pintype "passive"))
      (node (ref "C117") (pin "1") (pinfunction "1_1") (pintype "passive"))
      (node (ref "C118") (pin "1") (pinfunction "1_1") (pintype "passive"))
      (node (ref "C119") (pin "1") (pinfunction "1_1") (pintype "passive"))
      (node (ref "C120") (pin "1") (pinfunction "1_1") (pintype "passive"))
      (node (ref "C121") (pin "1") (pinfunction "1_1") (pintype "passive"))
      (node (ref "C122") (pin "1") (pinfunction "1_1") (pintype "passive"))
      (node (ref "C123") (pin "1") (pinfunction "1_1") (pintype "passive"))
      (node (ref "C124") (pin "1") (pinfunction "1_1") (pintype "passive"))
      (node (ref "C125") (pin "1") (pinfunction "1_1") (pintype "passive"))
      (node (ref "C126") (pin "1") (pinfunction "1_1") (pintype "passive"))
      (node (ref "C127") (pin "1") (pinfunction "1_1") (pintype "passive"))
      (node (ref "C128") (pin "1") (pinfunction "1_1") (pintype "passive"))
      (node (ref "P102") (pin "1") (pinfunction "1_1") (pintype "passive"))
      (node (ref "P102") (pin "2") (pinfunction "2_2") (pintype "passive"))
      (node (ref "P106") (pin "16") (pinfunction "16_16") (pintype "passive"))
      (node (ref "Q102") (pin "2") (pinfunction "S_2") (pintype "passive"))
      (node (ref "Q104") (pin "2") (pinfunction "S_2") (pintype "passive"))
      (node (ref "Q106") (pin "2") (pinfunction "S_2") (pintype "passive"))
      (node (ref "Q108") (pin "2") (pinfunction "S_2") (pintype "passive"))
      (node (ref "R104") (pin "1") (pinfunction "1_1") (pintype "passive"))
      (node (ref "R109") (pin "2") (pinfunction "2_2") (pintype "passive"))
      (node (ref "R110") (pin "1") (pinfunction "1_1") (pintype "passive"))
      (node (ref "R111") (pin "2") (pinfunction "2_2") (pintype "passive"))
      (node (ref "R113") (pin "1") (pinfunction "1_1") (pintype "passive"))
      (node (ref "R116") (pin "1") (pinfunction "1_1") (pintype "passive"))
      (node (ref "R119") (pin "1") (pinfunction "1_1") (pintype "passive"))
      (node (ref "R123") (pin "1") (pinfunction "1_1") (pintype "passive"))
      (node (ref "R124") (pin "1") (pinfunction "1_1") (pintype "passive"))
      (node (ref "R125") (pin "1") (pinfunction "1_1") (pintype "passive"))
      (node (ref "R126") (pin "1") (pinfunction "1_1") (pintype "passive"))
      (node (ref "R127") (pin "1") (pinfunction "1_1") (pintype "passive"))
      (node (ref "R128") (pin "1") (pinfunction "1_1") (pintype "passive"))
      (node (ref "R129") (pin "1") (pinfunction "1_1") (pintype "passive"))
      (node (ref "R130") (pin "1") (pinfunction "1_1") (pintype "passive"))
      (node (ref "R133") (pin "1") (pinfunction "1_1") (pintype "passive"))
      (node (ref "R136") (pin "1") (pinfunction "1_1") (pintype "passive"))
      (node (ref "U101") (pin "19") (pinfunction "DGND_19") (pintype "power_in"))
      (node (ref "U101") (pin "3") (pinfunction "DGND_3") (pintype "power_in"))
      (node (ref "U101") (pin "4") (pinfunction "AGND_4") (pintype "power_in"))
      (node (ref "U101") (pin "6") (pinfunction "VSS_6") (pintype "power_in"))
    )
    (net (code "61") (name "Net-(C105-Pad1)") (class "Default")
      (node (ref "C105") (pin "1") (pinfunction "1_1") (pintype "passive"))
      (node (ref "C106") (pin "1") (pinfunction "1_1") (pintype "passive"))
      (node (ref "C107") (pin "1") (pinfunction "1_1") (pintype "passive"))
      (node (ref "R108") (pin "4") (pinfunction "4_4") (pintype "passive"))
      (node (ref "R109") (pin "1") (pinfunction "1_1") (pintype "passive"))
      (node (ref "R110") (pin "2") (pinfunction "2_2") (pintype "passive"))
      (node (ref "R111") (pin "1") (pinfunction "1_1") (pintype "passive"))
    )
    (net (code "62") (name "Net-(C105-Pad2)") (class "Default")
      (node (ref "C105") (pin "2") (pinfunction "2_2") (pintype "passive"))
      (node (ref "P103") (pin "1") (pinfunction "1_1") (pintype "passive"))
      (node (ref "P103") (pin "2") (pinfunction "2_2") (pintype "passive"))
      (node (ref "R105") (pin "4") (pinfunction "4_4") (pintype "passive"))
      (node (ref "R112") (pin "2") (pinfunction "2_2") (pintype "passive"))
    )
    (net (code "63") (name "Net-(C106-Pad2)") (class "Default")
      (node (ref "C106") (pin "2") (pinfunction "2_2") (pintype "passive"))
      (node (ref "P104") (pin "1") (pinfunction "1_1") (pintype "passive"))
      (node (ref "P104") (pin "2") (pinfunction "2_2") (pintype "passive"))
      (node (ref "R106") (pin "4") (pinfunction "4_4") (pintype "passive"))
      (node (ref "R115") (pin "2") (pinfunction "2_2") (pintype "passive"))
    )
    (net (code "64") (name "Net-(C107-Pad2)") (class "Default")
      (node (ref "C107") (pin "2") (pinfunction "2_2") (pintype "passive"))
      (node (ref "P105") (pin "1") (pinfunction "1_1") (pintype "passive"))
      (node (ref "P105") (pin "2") (pinfunction "2_2") (pintype "passive"))
      (node (ref "R107") (pin "4") (pinfunction "4_4") (pintype "passive"))
      (node (ref "R118") (pin "2") (pinfunction "2_2") (pintype "passive"))
    )
    (net (code "65") (name "Net-(L101-Pad2)") (class "Default")
      (node (ref "L101") (pin "2") (pinfunction "2_2") (pintype "passive"))
      (node (ref "R105") (pin "1") (pinfunction "1_1") (pintype "passive"))
    )
    (net (code "66") (name "Net-(L102-Pad2)") (class "Default")
      (node (ref "L102") (pin "2") (pinfunction "2_2") (pintype "passive"))
      (node (ref "R106") (pin "1") (pinfunction "1_1") (pintype "passive"))
    )
    (net (code "67") (name "Net-(L103-Pad2)") (class "Default")
      (node (ref "L103") (pin "2") (pinfunction "2_2") (pintype "passive"))
      (node (ref "R107") (pin "1") (pinfunction "1_1") (pintype "passive"))
    )
    (net (code "68") (name "Net-(L104-Pad2)") (class "Default")
      (node (ref "L104") (pin "2") (pinfunction "2_2") (pintype "passive"))
      (node (ref "R108") (pin "1") (pinfunction "1_1") (pintype "passive"))
    )
    (net (code "69") (name "Net-(Q101-D)") (class "Default")
      (node (ref "Q101") (pin "3") (pinfunction "D_3") (pintype "passive"))
      (node (ref "Q103") (pin "3") (pinfunction "D_3") (pintype "passive"))
      (node (ref "Q105") (pin "3") (pinfunction "D_3") (pintype "passive"))
      (node (ref "Q107") (pin "3") (pinfunction "D_3") (pintype "passive"))
      (node (ref "R101") (pin "4") (pinfunction "4_4") (pintype "passive"))
      (node (ref "R102") (pin "2") (pinfunction "2_2") (pintype "passive"))
    )
    (net (code "70") (name "Net-(R102-Pad1)") (class "Default")
      (node (ref "R102") (pin "1") (pinfunction "1_1") (pintype "passive"))
      (node (ref "R103") (pin "2") (pinfunction "2_2") (pintype "passive"))
      (node (ref "R104") (pin "2") (pinfunction "2_2") (pintype "passive"))
    )
    (net (code "71") (name "Net-(R112-Pad1)") (class "Default")
      (node (ref "R112") (pin "1") (pinfunction "1_1") (pintype "passive"))
      (node (ref "R113") (pin "2") (pinfunction "2_2") (pintype "passive"))
      (node (ref "R114") (pin "2") (pinfunction "2_2") (pintype "passive"))
    )
    (net (code "72") (name "Net-(R115-Pad1)") (class "Default")
      (node (ref "R115") (pin "1") (pinfunction "1_1") (pintype "passive"))
      (node (ref "R116") (pin "2") (pinfunction "2_2") (pintype "passive"))
      (node (ref "R117") (pin "2") (pinfunction "2_2") (pintype "passive"))
    )
    (net (code "73") (name "Net-(R118-Pad1)") (class "Default")
      (node (ref "R118") (pin "1") (pinfunction "1_1") (pintype "passive"))
      (node (ref "R119") (pin "2") (pinfunction "2_2") (pintype "passive"))
      (node (ref "R120") (pin "2") (pinfunction "2_2") (pintype "passive"))
    )
    (net (code "74") (name "Net-(R135-TOP)") (class "Default")
      (node (ref "R134") (pin "1") (pinfunction "1_1") (pintype "passive"))
      (node (ref "R135") (pin "1") (pinfunction "TOP_1") (pintype "passive"))
    )
    (net (code "75") (name "Net-(R138-TOP)") (class "Default")
      (node (ref "R137") (pin "1") (pinfunction "1_1") (pintype "passive"))
      (node (ref "R138") (pin "1") (pinfunction "TOP_1") (pintype "passive"))
    )
    (net (code "76") (name "Net-(U101-REFIN{slash}OUT)") (class "Default")
      (node (ref "C120") (pin "2") (pinfunction "2_2") (pintype "passive"))
      (node (ref "U101") (pin "5") (pinfunction "REFIN/OUT_5") (pintype "bidirectional"))
    )
    (net (code "77") (name "Net-(U101-VIN0)") (class "Default")
      (node (ref "R121") (pin "1") (pinfunction "1_1") (pintype "passive"))
      (node (ref "R122") (pin "1") (pinfunction "1_1") (pintype "passive"))
      (node (ref "R130") (pin "2") (pinfunction "2_2") (pintype "passive"))
      (node (ref "U101") (pin "7") (pinfunction "VIN0_7") (pintype "input"))
    )
    (net (code "78") (name "Net-(U102-ADJ)") (class "Default")
      (node (ref "R133") (pin "2") (pinfunction "2_2") (pintype "passive"))
      (node (ref "R134") (pin "2") (pinfunction "2_2") (pintype "passive"))
      (node (ref "U102") (pin "3") (pinfunction "ADJ_3") (pintype "power_in"))
    )
    (net (code "79") (name "Net-(U103-ADJ)") (class "Default")
      (node (ref "R136") (pin "2") (pinfunction "2_2") (pintype "passive"))
      (node (ref "R137") (pin "2") (pinfunction "2_2") (pintype "passive"))
      (node (ref "U103") (pin "3") (pinfunction "ADJ_3") (pintype "power_in"))
    )
  )
)
